# IR_Schematic.net
KiCad netlist of a schematic drawn in EAGLE
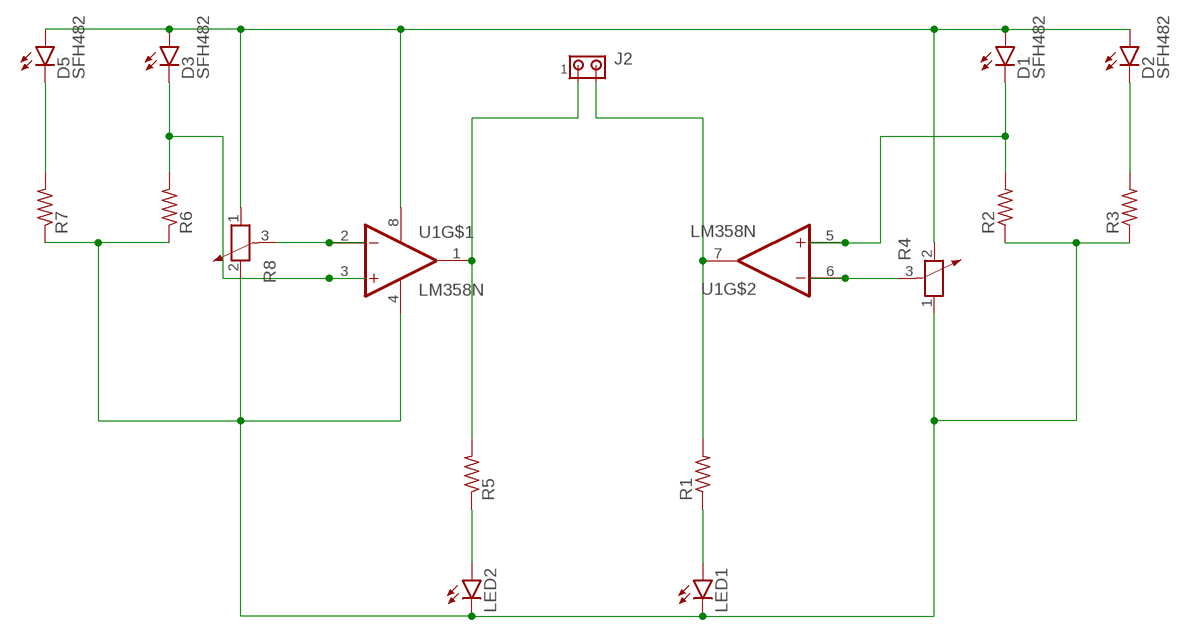
[diagram p0: schematic, sheet 1]

(export (version "E")
  (design (tool "Eeschema 10.0.6"))
  (components
    (comp (ref "D1")
      (value "SFH482")
      (footprint "eagle-import:SFH482")
      (libsource (lib "eagle-import") (part "SFH482"))
    )
    (comp (ref "D2")
      (value "SFH482")
      (footprint "eagle-import:SFH482")
      (libsource (lib "eagle-import") (part "SFH482"))
    )
    (comp (ref "D3")
      (value "SFH482")
      (footprint "eagle-import:SFH482")
      (libsource (lib "eagle-import") (part "SFH482"))
    )
    (comp (ref "D5")
      (value "SFH482")
      (footprint "eagle-import:SFH482")
      (libsource (lib "eagle-import") (part "SFH482"))
    )
    (comp (ref "J2")
      (value "MTA02-100")
      (footprint "eagle-import:10X02MTA")
      (libsource (lib "eagle-import") (part "MTA02-100"))
    )
    (comp (ref "LED1")
      (value "LED3MM")
      (footprint "eagle-import:LED3MM")
      (libsource (lib "eagle-import") (part "LED3MM"))
    )
    (comp (ref "LED2")
      (value "LED3MM")
      (footprint "eagle-import:LED3MM")
      (libsource (lib "eagle-import") (part "LED3MM"))
    )
    (comp (ref "R1")
      (value "R-US_0204/5")
      (footprint "eagle-import:0204_5")
      (libsource (lib "eagle-import") (part "R-US_0204/5"))
    )
    (comp (ref "R2")
      (value "R-US_0204/5")
      (footprint "eagle-import:0204_5")
      (libsource (lib "eagle-import") (part "R-US_0204/5"))
    )
    (comp (ref "R3")
      (value "R-US_0204/5")
      (footprint "eagle-import:0204_5")
      (libsource (lib "eagle-import") (part "R-US_0204/5"))
    )
    (comp (ref "R4")
      (value "POTENTIOMETER_PT-10")
      (footprint "eagle-import:PT-10")
      (libsource (lib "eagle-import") (part "POTENTIOMETER_PT-10"))
    )
    (comp (ref "R5")
      (value "R-US_0204/5")
      (footprint "eagle-import:0204_5")
      (libsource (lib "eagle-import") (part "R-US_0204/5"))
    )
    (comp (ref "R6")
      (value "R-US_0204/5")
      (footprint "eagle-import:0204_5")
      (libsource (lib "eagle-import") (part "R-US_0204/5"))
    )
    (comp (ref "R7")
      (value "R-US_0204/5")
      (footprint "eagle-import:0204_5")
      (libsource (lib "eagle-import") (part "R-US_0204/5"))
    )
    (comp (ref "R8")
      (value "POTENTIOMETER_PT-10")
      (footprint "eagle-import:PT-10")
      (libsource (lib "eagle-import") (part "POTENTIOMETER_PT-10"))
    )
    (comp (ref "U1")
      (value "LM358N")
      (footprint "eagle-import:DIP762W46P254L960H508Q8")
      (fields (field (name "MF") "Harris Corporation"))
      (libsource (lib "eagle-import") (part "LM358N"))
    )
  )
  (nets
    (net (code "1") (name "Net-(D1-C)") (class "Default")
      (node (ref "D1") (pin "K") (pinfunction "C_K") (pintype "passive"))
      (node (ref "R2") (pin "2") (pinfunction "2_2") (pintype "passive"))
      (node (ref "U1") (pin "5") (pinfunction "2IN+_5") (pintype "input"))
    )
    (net (code "2") (name "Net-(D2-C)") (class "Default")
      (node (ref "D2") (pin "K") (pinfunction "C_K") (pintype "passive"))
      (node (ref "R3") (pin "2") (pinfunction "2_2") (pintype "passive"))
    )
    (net (code "3") (name "Net-(D3-C)") (class "Default")
      (node (ref "D3") (pin "K") (pinfunction "C_K") (pintype "passive"))
      (node (ref "R6") (pin "2") (pinfunction "2_2") (pintype "passive"))
      (node (ref "U1") (pin "3") (pinfunction "1IN+_3") (pintype "input"))
    )
    (net (code "4") (name "Net-(D5-C)") (class "Default")
      (node (ref "D5") (pin "K") (pinfunction "C_K") (pintype "passive"))
      (node (ref "R7") (pin "2") (pinfunction "2_2") (pintype "passive"))
    )
    (net (code "5") (name "Net-(LED1-C)") (class "Default")
      (node (ref "LED1") (pin "K") (pinfunction "C_K") (pintype "passive"))
      (node (ref "LED2") (pin "K") (pinfunction "C_K") (pintype "passive"))
      (node (ref "R2") (pin "1") (pinfunction "1_1") (pintype "passive"))
      (node (ref "R3") (pin "1") (pinfunction "1_1") (pintype "passive"))
      (node (ref "R4") (pin "1") (pinfunction "1_1") (pintype "passive"))
      (node (ref "R6") (pin "1") (pinfunction "1_1") (pintype "passive"))
      (node (ref "R7") (pin "1") (pinfunction "1_1") (pintype "passive"))
      (node (ref "R8") (pin "2") (pinfunction "2_2") (pintype "passive"))
      (node (ref "U1") (pin "4") (pinfunction "GND_4") (pintype "power_in"))
    )
    (net (code "6") (name "Net-(LED1-PadA)") (class "Default")
      (node (ref "LED1") (pin "A") (pinfunction "A_A") (pintype "passive"))
      (node (ref "R1") (pin "1") (pinfunction "1_1") (pintype "passive"))
    )
    (net (code "7") (name "Net-(LED2-PadA)") (class "Default")
      (node (ref "LED2") (pin "A") (pinfunction "A_A") (pintype "passive"))
      (node (ref "R5") (pin "1") (pinfunction "1_1") (pintype "passive"))
    )
    (net (code "8") (name "Net-(U1A-1IN-)") (class "Default")
      (node (ref "R8") (pin "3") (pinfunction "3_3") (pintype "passive"))
      (node (ref "U1") (pin "2") (pinfunction "1IN-_2") (pintype "input"))
    )
    (net (code "9") (name "Net-(U1A-1OUT)") (class "Default")
      (node (ref "J2") (pin "1") (pinfunction "1_1") (pintype "passive"))
      (node (ref "R5") (pin "2") (pinfunction "2_2") (pintype "passive"))
      (node (ref "U1") (pin "1") (pinfunction "1OUT_1") (pintype "output"))
    )
    (net (code "10") (name "Net-(U1A-VCC)") (class "Default")
      (node (ref "D1") (pin "A") (pinfunction "A_A") (pintype "passive"))
      (node (ref "D2") (pin "A") (pinfunction "A_A") (pintype "passive"))
      (node (ref "D3") (pin "A") (pinfunction "A_A") (pintype "passive"))
      (node (ref "D5") (pin "A") (pinfunction "A_A") (pintype "passive"))
      (node (ref "R4") (pin "2") (pinfunction "2_2") (pintype "passive"))
      (node (ref "R8") (pin "1") (pinfunction "1_1") (pintype "passive"))
      (node (ref "U1") (pin "8") (pinfunction "VCC_8") (pintype "power_in"))
    )
    (net (code "11") (name "Net-(U1B-2IN-)") (class "Default")
      (node (ref "R4") (pin "3") (pinfunction "3_3") (pintype "passive"))
      (node (ref "U1") (pin "6") (pinfunction "2IN-_6") (pintype "input"))
    )
    (net (code "12") (name "Net-(U1B-2OUT)") (class "Default")
      (node (ref "J2") (pin "2") (pinfunction "2_2") (pintype "passive"))
      (node (ref "R1") (pin "2") (pinfunction "2_2") (pintype "passive"))
      (node (ref "U1") (pin "7") (pinfunction "2OUT_7") (pintype "output"))
    )
  )
)
